# Adafruit_Proto_Under_Plate_PiCowBell.net
KiCad netlist of a schematic drawn in EAGLE
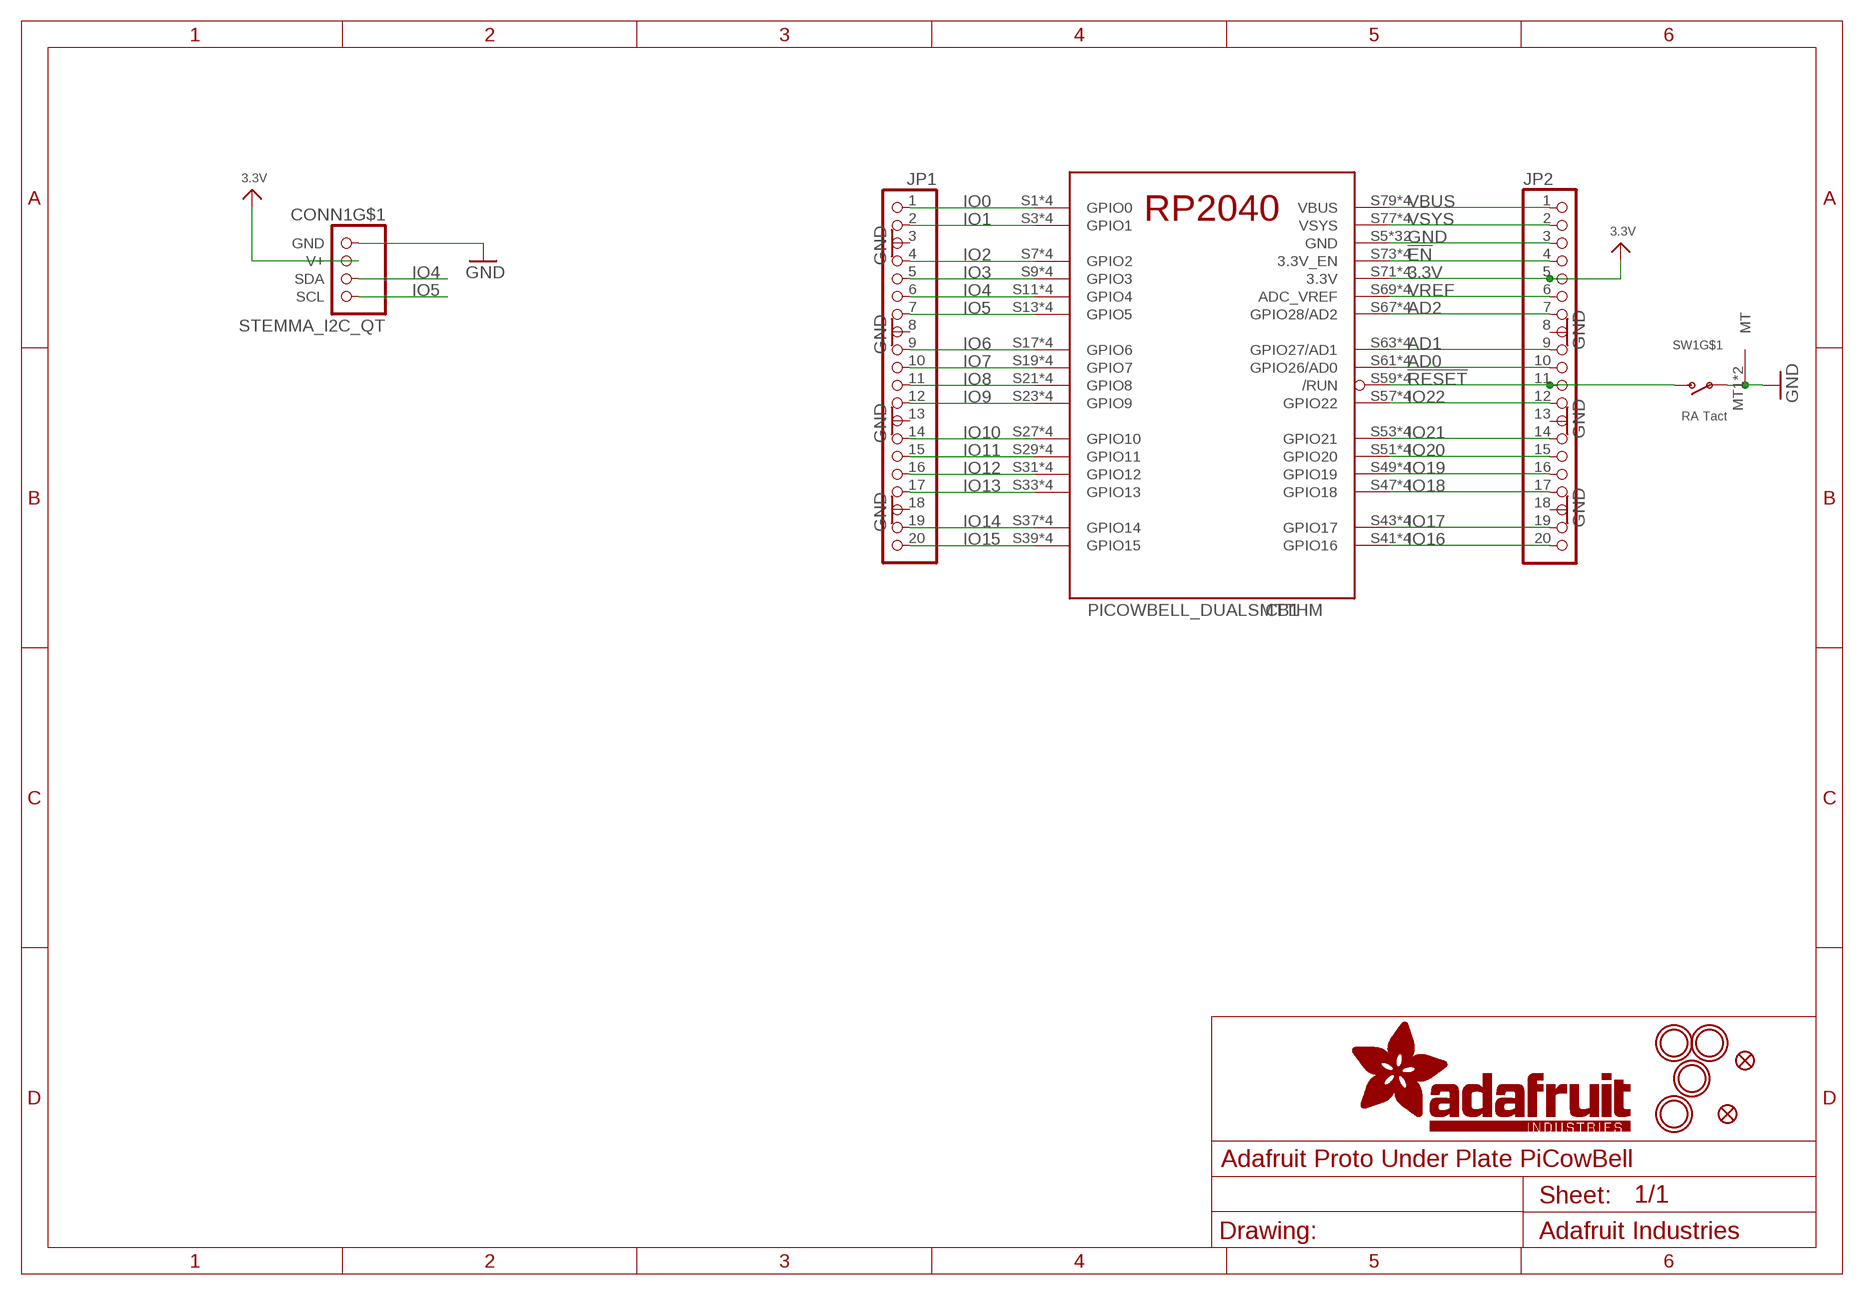
[diagram p0: schematic, sheet 1]

(export (version "E")
  (design (tool "Eeschema 10.0.6"))
  (components
    (comp (ref "CB1")
      (value "PICOWBELL_DUALSMTTHM")
      (footprint "eagle-import:PICOWBELL_DUALSMTTHM")
      (libsource (lib "eagle-import") (part "PICOWBELL_DUALSMTTHM"))
    )
    (comp (ref "CONN1")
      (value "STEMMA_I2C_QT")
      (footprint "eagle-import:JST_SH4")
      (libsource (lib "eagle-import") (part "STEMMA_I2C_QT"))
    )
    (comp (ref "FID1")
      (value "FIDUCIAL_1MM")
      (footprint "eagle-import:FIDUCIAL_1MM")
      (libsource (lib "eagle-import") (part "FIDUCIAL_1MM"))
    )
    (comp (ref "FID2")
      (value "FIDUCIAL_1MM")
      (footprint "eagle-import:FIDUCIAL_1MM")
      (libsource (lib "eagle-import") (part "FIDUCIAL_1MM"))
    )
    (comp (ref "JP1")
      (value "HEADER-1X20_70MIL")
      (footprint "eagle-import:1X20_ROUND_70MIL")
      (libsource (lib "eagle-import") (part "HEADER-1X20_70MIL"))
    )
    (comp (ref "JP2")
      (value "HEADER-1X20_70MIL")
      (footprint "eagle-import:1X20_ROUND_70MIL")
      (libsource (lib "eagle-import") (part "HEADER-1X20_70MIL"))
    )
    (comp (ref "SW1")
      (value "RA Tact")
      (footprint "eagle-import:SPST_TACTILE_RA")
      (libsource (lib "eagle-import") (part "SWITCH_SPST_MNT_TACT_RA"))
    )
    (comp (ref "U$5")
      (value "MOUNTINGHOLE2.5")
      (footprint "eagle-import:MOUNTINGHOLE_2.5_PLATED")
      (libsource (lib "eagle-import") (part "MOUNTINGHOLE2.5"))
    )
    (comp (ref "U$7")
      (value "MOUNTINGHOLE2.5")
      (footprint "eagle-import:MOUNTINGHOLE_2.5_PLATED")
      (libsource (lib "eagle-import") (part "MOUNTINGHOLE2.5"))
    )
    (comp (ref "U$8")
      (value "MOUNTINGHOLE2.5")
      (footprint "eagle-import:MOUNTINGHOLE_2.5_PLATED")
      (libsource (lib "eagle-import") (part "MOUNTINGHOLE2.5"))
    )
    (comp (ref "U$9")
      (value "MOUNTINGHOLE2.5")
      (footprint "eagle-import:MOUNTINGHOLE_2.5_PLATED")
      (libsource (lib "eagle-import") (part "MOUNTINGHOLE2.5"))
    )
  )
  (nets
    (net (code "1") (name "/AD0") (class "Default")
      (node (ref "CB1") (pin "S61") (pinfunction "GPIO26/AD0_S61") (pintype "bidirectional"))
      (node (ref "CB1") (pin "S62") (pinfunction "GPIO26/AD0_S62") (pintype "bidirectional"))
      (node (ref "CB1") (pin "T61") (pinfunction "GPIO26/AD0_T61") (pintype "bidirectional"))
      (node (ref "CB1") (pin "T62") (pinfunction "GPIO26/AD0_T62") (pintype "bidirectional"))
      (node (ref "JP2") (pin "10") (pinfunction "10_10") (pintype "passive"))
    )
    (net (code "2") (name "/AD1") (class "Default")
      (node (ref "CB1") (pin "S63") (pinfunction "GPIO27/AD1_S63") (pintype "bidirectional"))
      (node (ref "CB1") (pin "S64") (pinfunction "GPIO27/AD1_S64") (pintype "bidirectional"))
      (node (ref "CB1") (pin "T63") (pinfunction "GPIO27/AD1_T63") (pintype "bidirectional"))
      (node (ref "CB1") (pin "T64") (pinfunction "GPIO27/AD1_T64") (pintype "bidirectional"))
      (node (ref "JP2") (pin "9") (pinfunction "9_9") (pintype "passive"))
    )
    (net (code "3") (name "/AD2") (class "Default")
      (node (ref "CB1") (pin "S67") (pinfunction "GPIO28/AD2_S67") (pintype "bidirectional"))
      (node (ref "CB1") (pin "S68") (pinfunction "GPIO28/AD2_S68") (pintype "bidirectional"))
      (node (ref "CB1") (pin "T67") (pinfunction "GPIO28/AD2_T67") (pintype "bidirectional"))
      (node (ref "CB1") (pin "T68") (pinfunction "GPIO28/AD2_T68") (pintype "bidirectional"))
      (node (ref "JP2") (pin "7") (pinfunction "7_7") (pintype "passive"))
    )
    (net (code "4") (name "/IO0") (class "Default")
      (node (ref "CB1") (pin "S1") (pinfunction "GPIO0_S1") (pintype "bidirectional"))
      (node (ref "CB1") (pin "S2") (pinfunction "GPIO0_S2") (pintype "bidirectional"))
      (node (ref "CB1") (pin "T1") (pinfunction "GPIO0_T1") (pintype "bidirectional"))
      (node (ref "CB1") (pin "T2") (pinfunction "GPIO0_T2") (pintype "bidirectional"))
      (node (ref "JP1") (pin "1") (pinfunction "1_1") (pintype "passive"))
    )
    (net (code "5") (name "/IO1") (class "Default")
      (node (ref "CB1") (pin "S3") (pinfunction "GPIO1_S3") (pintype "bidirectional"))
      (node (ref "CB1") (pin "S4") (pinfunction "GPIO1_S4") (pintype "bidirectional"))
      (node (ref "CB1") (pin "T3") (pinfunction "GPIO1_T3") (pintype "bidirectional"))
      (node (ref "CB1") (pin "T4") (pinfunction "GPIO1_T4") (pintype "bidirectional"))
      (node (ref "JP1") (pin "2") (pinfunction "2_2") (pintype "passive"))
    )
    (net (code "6") (name "/IO2") (class "Default")
      (node (ref "CB1") (pin "S7") (pinfunction "GPIO2_S7") (pintype "bidirectional"))
      (node (ref "CB1") (pin "S8") (pinfunction "GPIO2_S8") (pintype "bidirectional"))
      (node (ref "CB1") (pin "T7") (pinfunction "GPIO2_T7") (pintype "bidirectional"))
      (node (ref "CB1") (pin "T8") (pinfunction "GPIO2_T8") (pintype "bidirectional"))
      (node (ref "JP1") (pin "4") (pinfunction "4_4") (pintype "passive"))
    )
    (net (code "7") (name "/IO3") (class "Default")
      (node (ref "CB1") (pin "S10") (pinfunction "GPIO3_S10") (pintype "bidirectional"))
      (node (ref "CB1") (pin "S9") (pinfunction "GPIO3_S9") (pintype "bidirectional"))
      (node (ref "CB1") (pin "T10") (pinfunction "GPIO3_T10") (pintype "bidirectional"))
      (node (ref "CB1") (pin "T9") (pinfunction "GPIO3_T9") (pintype "bidirectional"))
      (node (ref "JP1") (pin "5") (pinfunction "5_5") (pintype "passive"))
    )
    (net (code "8") (name "/IO4") (class "Default")
      (node (ref "CB1") (pin "S11") (pinfunction "GPIO4_S11") (pintype "bidirectional"))
      (node (ref "CB1") (pin "S12") (pinfunction "GPIO4_S12") (pintype "bidirectional"))
      (node (ref "CB1") (pin "T11") (pinfunction "GPIO4_T11") (pintype "bidirectional"))
      (node (ref "CB1") (pin "T12") (pinfunction "GPIO4_T12") (pintype "bidirectional"))
      (node (ref "CONN1") (pin "3") (pinfunction "SDA_3") (pintype "passive"))
      (node (ref "JP1") (pin "6") (pinfunction "6_6") (pintype "passive"))
    )
    (net (code "9") (name "/IO5") (class "Default")
      (node (ref "CB1") (pin "S13") (pinfunction "GPIO5_S13") (pintype "bidirectional"))
      (node (ref "CB1") (pin "S14") (pinfunction "GPIO5_S14") (pintype "bidirectional"))
      (node (ref "CB1") (pin "T13") (pinfunction "GPIO5_T13") (pintype "bidirectional"))
      (node (ref "CB1") (pin "T14") (pinfunction "GPIO5_T14") (pintype "bidirectional"))
      (node (ref "CONN1") (pin "4") (pinfunction "SCL_4") (pintype "passive"))
      (node (ref "JP1") (pin "7") (pinfunction "7_7") (pintype "passive"))
    )
    (net (code "10") (name "/IO6") (class "Default")
      (node (ref "CB1") (pin "S17") (pinfunction "GPIO6_S17") (pintype "bidirectional"))
      (node (ref "CB1") (pin "S18") (pinfunction "GPIO6_S18") (pintype "bidirectional"))
      (node (ref "CB1") (pin "T17") (pinfunction "GPIO6_T17") (pintype "bidirectional"))
      (node (ref "CB1") (pin "T18") (pinfunction "GPIO6_T18") (pintype "bidirectional"))
      (node (ref "JP1") (pin "9") (pinfunction "9_9") (pintype "passive"))
    )
    (net (code "11") (name "/IO7") (class "Default")
      (node (ref "CB1") (pin "S19") (pinfunction "GPIO7_S19") (pintype "bidirectional"))
      (node (ref "CB1") (pin "S20") (pinfunction "GPIO7_S20") (pintype "bidirectional"))
      (node (ref "CB1") (pin "T19") (pinfunction "GPIO7_T19") (pintype "bidirectional"))
      (node (ref "CB1") (pin "T20") (pinfunction "GPIO7_T20") (pintype "bidirectional"))
      (node (ref "JP1") (pin "10") (pinfunction "10_10") (pintype "passive"))
    )
    (net (code "12") (name "/IO8") (class "Default")
      (node (ref "CB1") (pin "S21") (pinfunction "GPIO8_S21") (pintype "bidirectional"))
      (node (ref "CB1") (pin "S22") (pinfunction "GPIO8_S22") (pintype "bidirectional"))
      (node (ref "CB1") (pin "T21") (pinfunction "GPIO8_T21") (pintype "bidirectional"))
      (node (ref "CB1") (pin "T22") (pinfunction "GPIO8_T22") (pintype "bidirectional"))
      (node (ref "JP1") (pin "11") (pinfunction "11_11") (pintype "passive"))
    )
    (net (code "13") (name "/IO9") (class "Default")
      (node (ref "CB1") (pin "S23") (pinfunction "GPIO9_S23") (pintype "bidirectional"))
      (node (ref "CB1") (pin "S24") (pinfunction "GPIO9_S24") (pintype "bidirectional"))
      (node (ref "CB1") (pin "T23") (pinfunction "GPIO9_T23") (pintype "bidirectional"))
      (node (ref "CB1") (pin "T24") (pinfunction "GPIO9_T24") (pintype "bidirectional"))
      (node (ref "JP1") (pin "12") (pinfunction "12_12") (pintype "passive"))
    )
    (net (code "14") (name "/IO10") (class "Default")
      (node (ref "CB1") (pin "S27") (pinfunction "GPIO10_S27") (pintype "bidirectional"))
      (node (ref "CB1") (pin "S28") (pinfunction "GPIO10_S28") (pintype "bidirectional"))
      (node (ref "CB1") (pin "T27") (pinfunction "GPIO10_T27") (pintype "bidirectional"))
      (node (ref "CB1") (pin "T28") (pinfunction "GPIO10_T28") (pintype "bidirectional"))
      (node (ref "JP1") (pin "14") (pinfunction "14_14") (pintype "passive"))
    )
    (net (code "15") (name "/IO11") (class "Default")
      (node (ref "CB1") (pin "S29") (pinfunction "GPIO11_S29") (pintype "bidirectional"))
      (node (ref "CB1") (pin "S30") (pinfunction "GPIO11_S30") (pintype "bidirectional"))
      (node (ref "CB1") (pin "T29") (pinfunction "GPIO11_T29") (pintype "bidirectional"))
      (node (ref "CB1") (pin "T30") (pinfunction "GPIO11_T30") (pintype "bidirectional"))
      (node (ref "JP1") (pin "15") (pinfunction "15_15") (pintype "passive"))
    )
    (net (code "16") (name "/IO12") (class "Default")
      (node (ref "CB1") (pin "S31") (pinfunction "GPIO12_S31") (pintype "bidirectional"))
      (node (ref "CB1") (pin "S32") (pinfunction "GPIO12_S32") (pintype "bidirectional"))
      (node (ref "CB1") (pin "T31") (pinfunction "GPIO12_T31") (pintype "bidirectional"))
      (node (ref "CB1") (pin "T32") (pinfunction "GPIO12_T32") (pintype "bidirectional"))
      (node (ref "JP1") (pin "16") (pinfunction "16_16") (pintype "passive"))
    )
    (net (code "17") (name "/IO13") (class "Default")
      (node (ref "CB1") (pin "S33") (pinfunction "GPIO13_S33") (pintype "bidirectional"))
      (node (ref "CB1") (pin "S34") (pinfunction "GPIO13_S34") (pintype "bidirectional"))
      (node (ref "CB1") (pin "T33") (pinfunction "GPIO13_T33") (pintype "bidirectional"))
      (node (ref "CB1") (pin "T34") (pinfunction "GPIO13_T34") (pintype "bidirectional"))
      (node (ref "JP1") (pin "17") (pinfunction "17_17") (pintype "passive"))
    )
    (net (code "18") (name "/IO14") (class "Default")
      (node (ref "CB1") (pin "S37") (pinfunction "GPIO14_S37") (pintype "bidirectional"))
      (node (ref "CB1") (pin "S38") (pinfunction "GPIO14_S38") (pintype "bidirectional"))
      (node (ref "CB1") (pin "T37") (pinfunction "GPIO14_T37") (pintype "bidirectional"))
      (node (ref "CB1") (pin "T38") (pinfunction "GPIO14_T38") (pintype "bidirectional"))
      (node (ref "JP1") (pin "19") (pinfunction "19_19") (pintype "passive"))
    )
    (net (code "19") (name "/IO15") (class "Default")
      (node (ref "CB1") (pin "S39") (pinfunction "GPIO15_S39") (pintype "bidirectional"))
      (node (ref "CB1") (pin "S40") (pinfunction "GPIO15_S40") (pintype "bidirectional"))
      (node (ref "CB1") (pin "T39") (pinfunction "GPIO15_T39") (pintype "bidirectional"))
      (node (ref "CB1") (pin "T40") (pinfunction "GPIO15_T40") (pintype "bidirectional"))
      (node (ref "JP1") (pin "20") (pinfunction "20_20") (pintype "passive"))
    )
    (net (code "20") (name "/IO16") (class "Default")
      (node (ref "CB1") (pin "S41") (pinfunction "GPIO16_S41") (pintype "bidirectional"))
      (node (ref "CB1") (pin "S42") (pinfunction "GPIO16_S42") (pintype "bidirectional"))
      (node (ref "CB1") (pin "T41") (pinfunction "GPIO16_T41") (pintype "bidirectional"))
      (node (ref "CB1") (pin "T42") (pinfunction "GPIO16_T42") (pintype "bidirectional"))
      (node (ref "JP2") (pin "20") (pinfunction "20_20") (pintype "passive"))
    )
    (net (code "21") (name "/IO17") (class "Default")
      (node (ref "CB1") (pin "S43") (pinfunction "GPIO17_S43") (pintype "bidirectional"))
      (node (ref "CB1") (pin "S44") (pinfunction "GPIO17_S44") (pintype "bidirectional"))
      (node (ref "CB1") (pin "T43") (pinfunction "GPIO17_T43") (pintype "bidirectional"))
      (node (ref "CB1") (pin "T44") (pinfunction "GPIO17_T44") (pintype "bidirectional"))
      (node (ref "JP2") (pin "19") (pinfunction "19_19") (pintype "passive"))
    )
    (net (code "22") (name "/IO18") (class "Default")
      (node (ref "CB1") (pin "S47") (pinfunction "GPIO18_S47") (pintype "bidirectional"))
      (node (ref "CB1") (pin "S48") (pinfunction "GPIO18_S48") (pintype "bidirectional"))
      (node (ref "CB1") (pin "T47") (pinfunction "GPIO18_T47") (pintype "bidirectional"))
      (node (ref "CB1") (pin "T48") (pinfunction "GPIO18_T48") (pintype "bidirectional"))
      (node (ref "JP2") (pin "17") (pinfunction "17_17") (pintype "passive"))
    )
    (net (code "23") (name "/IO19") (class "Default")
      (node (ref "CB1") (pin "S49") (pinfunction "GPIO19_S49") (pintype "bidirectional"))
      (node (ref "CB1") (pin "S50") (pinfunction "GPIO19_S50") (pintype "bidirectional"))
      (node (ref "CB1") (pin "T49") (pinfunction "GPIO19_T49") (pintype "bidirectional"))
      (node (ref "CB1") (pin "T50") (pinfunction "GPIO19_T50") (pintype "bidirectional"))
      (node (ref "JP2") (pin "16") (pinfunction "16_16") (pintype "passive"))
    )
    (net (code "24") (name "/IO20") (class "Default")
      (node (ref "CB1") (pin "S51") (pinfunction "GPIO20_S51") (pintype "bidirectional"))
      (node (ref "CB1") (pin "S52") (pinfunction "GPIO20_S52") (pintype "bidirectional"))
      (node (ref "CB1") (pin "T51") (pinfunction "GPIO20_T51") (pintype "bidirectional"))
      (node (ref "CB1") (pin "T52") (pinfunction "GPIO20_T52") (pintype "bidirectional"))
      (node (ref "JP2") (pin "15") (pinfunction "15_15") (pintype "passive"))
    )
    (net (code "25") (name "/IO21") (class "Default")
      (node (ref "CB1") (pin "S53") (pinfunction "GPIO21_S53") (pintype "bidirectional"))
      (node (ref "CB1") (pin "S54") (pinfunction "GPIO21_S54") (pintype "bidirectional"))
      (node (ref "CB1") (pin "T53") (pinfunction "GPIO21_T53") (pintype "bidirectional"))
      (node (ref "CB1") (pin "T54") (pinfunction "GPIO21_T54") (pintype "bidirectional"))
      (node (ref "JP2") (pin "14") (pinfunction "14_14") (pintype "passive"))
    )
    (net (code "26") (name "/IO22") (class "Default")
      (node (ref "CB1") (pin "S57") (pinfunction "GPIO22_S57") (pintype "bidirectional"))
      (node (ref "CB1") (pin "S58") (pinfunction "GPIO22_S58") (pintype "bidirectional"))
      (node (ref "CB1") (pin "T57") (pinfunction "GPIO22_T57") (pintype "bidirectional"))
      (node (ref "CB1") (pin "T58") (pinfunction "GPIO22_T58") (pintype "bidirectional"))
      (node (ref "JP2") (pin "12") (pinfunction "12_12") (pintype "passive"))
    )
    (net (code "27") (name "/VBUS") (class "Default")
      (node (ref "CB1") (pin "S79") (pinfunction "VBUS_S79") (pintype "power_in"))
      (node (ref "CB1") (pin "S80") (pinfunction "VBUS_S80") (pintype "power_in"))
      (node (ref "CB1") (pin "T79") (pinfunction "VBUS_T79") (pintype "power_in"))
      (node (ref "CB1") (pin "T80") (pinfunction "VBUS_T80") (pintype "power_in"))
      (node (ref "JP2") (pin "1") (pinfunction "1_1") (pintype "passive"))
    )
    (net (code "28") (name "/VREF") (class "Default")
      (node (ref "CB1") (pin "S69") (pinfunction "ADC_VREF_S69") (pintype "passive"))
      (node (ref "CB1") (pin "S70") (pinfunction "ADC_VREF_S70") (pintype "passive"))
      (node (ref "CB1") (pin "T69") (pinfunction "ADC_VREF_T69") (pintype "passive"))
      (node (ref "CB1") (pin "T70") (pinfunction "ADC_VREF_T70") (pintype "passive"))
      (node (ref "JP2") (pin "6") (pinfunction "6_6") (pintype "passive"))
    )
    (net (code "29") (name "/VSYS") (class "Default")
      (node (ref "CB1") (pin "S77") (pinfunction "VSYS_S77") (pintype "power_in"))
      (node (ref "CB1") (pin "S78") (pinfunction "VSYS_S78") (pintype "power_in"))
      (node (ref "CB1") (pin "T77") (pinfunction "VSYS_T77") (pintype "power_in"))
      (node (ref "CB1") (pin "T78") (pinfunction "VSYS_T78") (pintype "power_in"))
      (node (ref "JP2") (pin "2") (pinfunction "2_2") (pintype "passive"))
    )
    (net (code "30") (name "/~{EN}") (class "Default")
      (node (ref "CB1") (pin "S73") (pinfunction "3.3V_EN_S73") (pintype "passive"))
      (node (ref "CB1") (pin "S74") (pinfunction "3.3V_EN_S74") (pintype "passive"))
      (node (ref "CB1") (pin "T73") (pinfunction "3.3V_EN_T73") (pintype "passive"))
      (node (ref "CB1") (pin "T74") (pinfunction "3.3V_EN_T74") (pintype "passive"))
      (node (ref "JP2") (pin "4") (pinfunction "4_4") (pintype "passive"))
    )
    (net (code "31") (name "/~{RESET}") (class "Default")
      (node (ref "CB1") (pin "S59") (pinfunction "/RUN_S59") (pintype "bidirectional"))
      (node (ref "CB1") (pin "S60") (pinfunction "/RUN_S60") (pintype "bidirectional"))
      (node (ref "CB1") (pin "T59") (pinfunction "/RUN_T59") (pintype "bidirectional"))
      (node (ref "CB1") (pin "T60") (pinfunction "/RUN_T60") (pintype "bidirectional"))
      (node (ref "JP2") (pin "11") (pinfunction "11_11") (pintype "passive"))
      (node (ref "SW1") (pin "2") (pinfunction "S_2") (pintype "passive"))
    )
    (net (code "32") (name "3.3V") (class "Default")
      (node (ref "CB1") (pin "S71") (pinfunction "3.3V_S71") (pintype "power_in"))
      (node (ref "CB1") (pin "S72") (pinfunction "3.3V_S72") (pintype "power_in"))
      (node (ref "CB1") (pin "T71") (pinfunction "3.3V_T71") (pintype "power_in"))
      (node (ref "CB1") (pin "T72") (pinfunction "3.3V_T72") (pintype "power_in"))
      (node (ref "CONN1") (pin "2") (pinfunction "V+_2") (pintype "passive"))
      (node (ref "JP2") (pin "5") (pinfunction "5_5") (pintype "passive"))
    )
    (net (code "33") (name "GND") (class "Default")
      (node (ref "CB1") (pin "S15") (pinfunction "GND_S15") (pintype "power_in"))
      (node (ref "CB1") (pin "S16") (pinfunction "GND_S16") (pintype "power_in"))
      (node (ref "CB1") (pin "S25") (pinfunction "GND_S25") (pintype "power_in"))
      (node (ref "CB1") (pin "S26") (pinfunction "GND_S26") (pintype "power_in"))
      (node (ref "CB1") (pin "S35") (pinfunction "GND_S35") (pintype "power_in"))
      (node (ref "CB1") (pin "S36") (pinfunction "GND_S36") (pintype "power_in"))
      (node (ref "CB1") (pin "S45") (pinfunction "GND_S45") (pintype "power_in"))
      (node (ref "CB1") (pin "S46") (pinfunction "GND_S46") (pintype "power_in"))
      (node (ref "CB1") (pin "S5") (pinfunction "GND_S5") (pintype "power_in"))
      (node (ref "CB1") (pin "S55") (pinfunction "GND_S55") (pintype "power_in"))
      (node (ref "CB1") (pin "S56") (pinfunction "GND_S56") (pintype "power_in"))
      (node (ref "CB1") (pin "S6") (pinfunction "GND_S6") (pintype "power_in"))
      (node (ref "CB1") (pin "S65") (pinfunction "GND_S65") (pintype "power_in"))
      (node (ref "CB1") (pin "S66") (pinfunction "GND_S66") (pintype "power_in"))
      (node (ref "CB1") (pin "S75") (pinfunction "GND_S75") (pintype "power_in"))
      (node (ref "CB1") (pin "S76") (pinfunction "GND_S76") (pintype "power_in"))
      (node (ref "CB1") (pin "T15") (pinfunction "GND_T15") (pintype "power_in"))
      (node (ref "CB1") (pin "T16") (pinfunction "GND_T16") (pintype "power_in"))
      (node (ref "CB1") (pin "T25") (pinfunction "GND_T25") (pintype "power_in"))
      (node (ref "CB1") (pin "T26") (pinfunction "GND_T26") (pintype "power_in"))
      (node (ref "CB1") (pin "T35") (pinfunction "GND_T35") (pintype "power_in"))
      (node (ref "CB1") (pin "T36") (pinfunction "GND_T36") (pintype "power_in"))
      (node (ref "CB1") (pin "T45") (pinfunction "GND_T45") (pintype "power_in"))
      (node (ref "CB1") (pin "T46") (pinfunction "GND_T46") (pintype "power_in"))
      (node (ref "CB1") (pin "T5") (pinfunction "GND_T5") (pintype "power_in"))
      (node (ref "CB1") (pin "T55") (pinfunction "GND_T55") (pintype "power_in"))
      (node (ref "CB1") (pin "T56") (pinfunction "GND_T56") (pintype "power_in"))
      (node (ref "CB1") (pin "T6") (pinfunction "GND_T6") (pintype "power_in"))
      (node (ref "CB1") (pin "T65") (pinfunction "GND_T65") (pintype "power_in"))
      (node (ref "CB1") (pin "T66") (pinfunction "GND_T66") (pintype "power_in"))
      (node (ref "CB1") (pin "T75") (pinfunction "GND_T75") (pintype "power_in"))
      (node (ref "CB1") (pin "T76") (pinfunction "GND_T76") (pintype "power_in"))
      (node (ref "CONN1") (pin "1") (pinfunction "GND_1") (pintype "passive"))
      (node (ref "JP1") (pin "13") (pinfunction "13_13") (pintype "passive"))
      (node (ref "JP1") (pin "18") (pinfunction "18_18") (pintype "passive"))
      (node (ref "JP1") (pin "3") (pinfunction "3_3") (pintype "passive"))
      (node (ref "JP1") (pin "8") (pinfunction "8_8") (pintype "passive"))
      (node (ref "JP2") (pin "13") (pinfunction "13_13") (pintype "passive"))
      (node (ref "JP2") (pin "18") (pinfunction "18_18") (pintype "passive"))
      (node (ref "JP2") (pin "3") (pinfunction "3_3") (pintype "passive"))
      (node (ref "JP2") (pin "8") (pinfunction "8_8") (pintype "passive"))
      (node (ref "SW1") (pin "1") (pinfunction "P_1") (pintype "passive"))
      (node (ref "SW1") (pin "MT1") (pinfunction "MT_MT1") (pintype "bidirectional"))
      (node (ref "SW1") (pin "MT2") (pinfunction "MT_MT2") (pintype "bidirectional"))
    )
  )
)
